# Sensor_Board.net
KiCad netlist of a schematic drawn in EAGLE
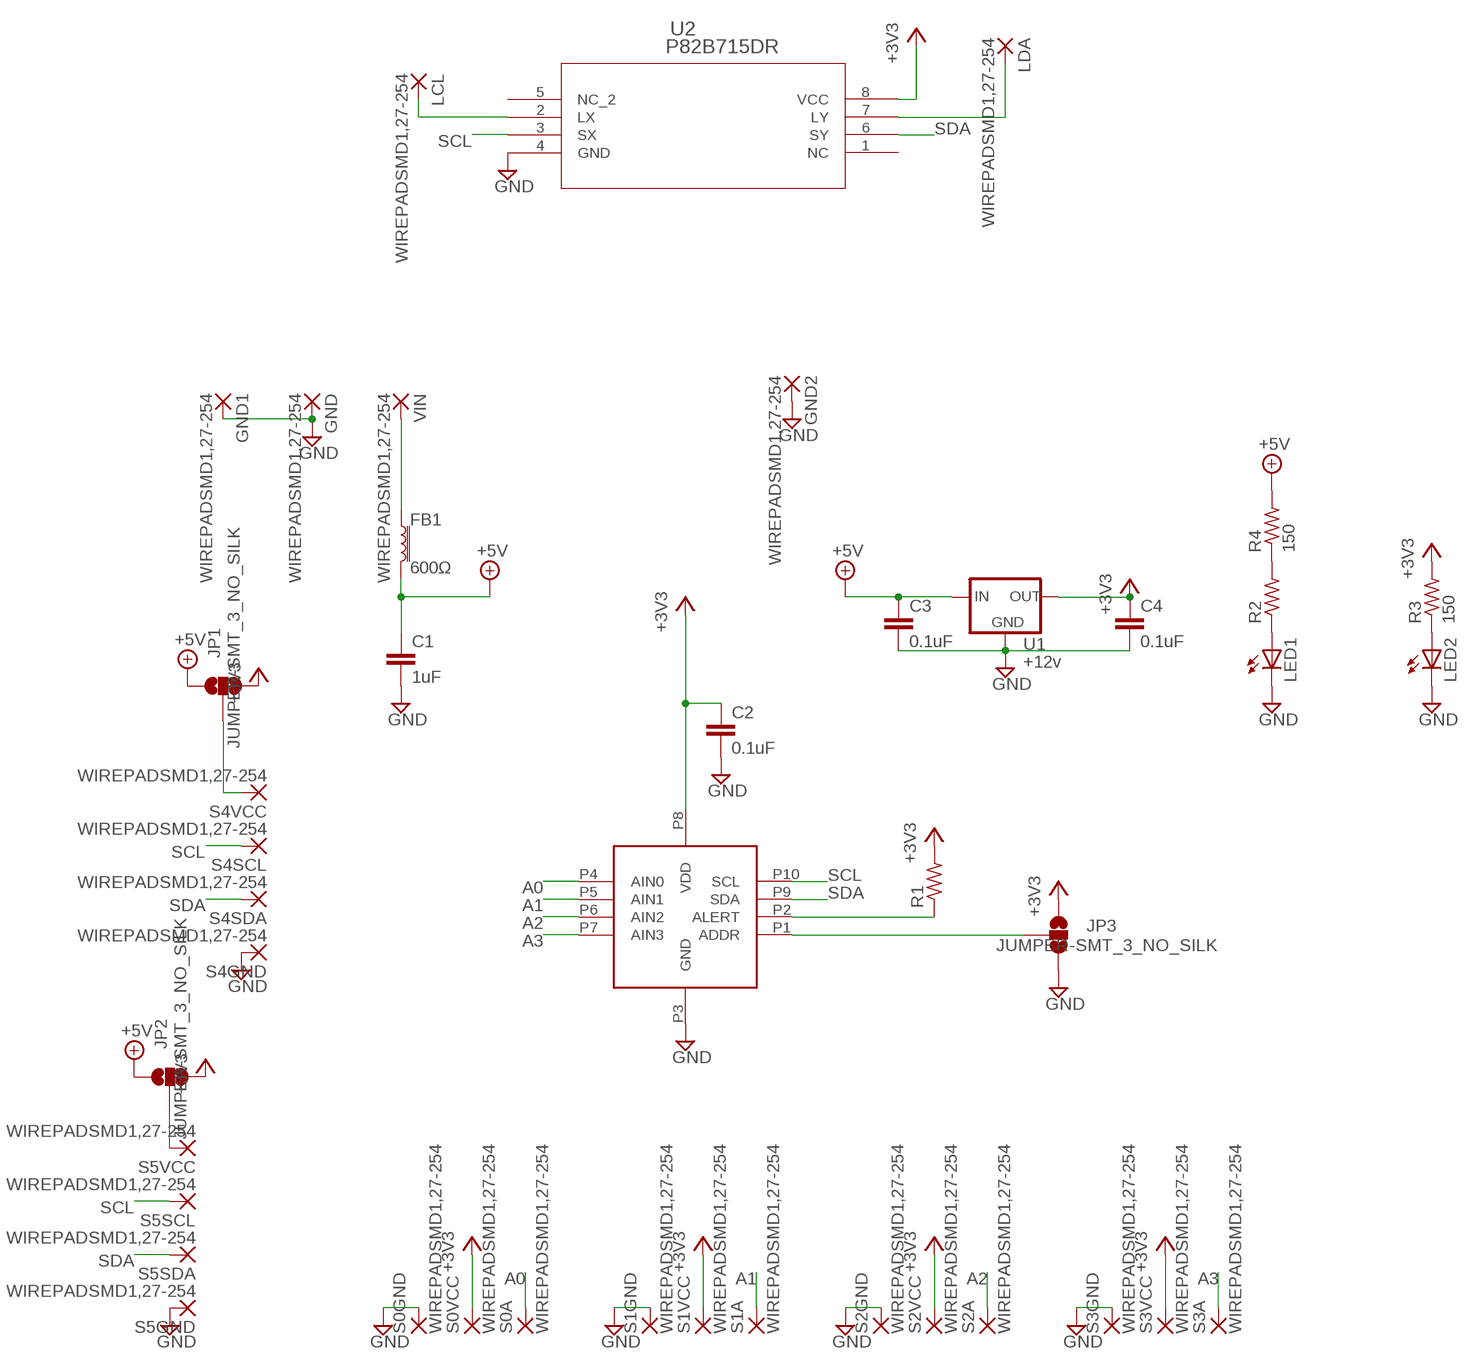
[diagram p0: schematic, sheet 1]

(export (version "E")
  (design (tool "Eeschema 10.0.6"))
  (components
    (comp (ref "C1")
      (value "1uF")
      (footprint "eagle-import:C0805")
      (libsource (lib "eagle-import") (part "C-EUC0805"))
    )
    (comp (ref "C2")
      (value "0.1uF")
      (footprint "eagle-import:C0805")
      (libsource (lib "eagle-import") (part "C-EUC0805"))
    )
    (comp (ref "C3")
      (value "0.1uF")
      (footprint "eagle-import:C0805")
      (libsource (lib "eagle-import") (part "C-EUC0805"))
    )
    (comp (ref "C4")
      (value "0.1uF")
      (footprint "eagle-import:C0805")
      (libsource (lib "eagle-import") (part "C-EUC0805"))
    )
    (comp (ref "FB1")
      (value "600Ω")
      (footprint "eagle-import:0805")
      (libsource (lib "eagle-import") (part "FERRITE_BEAD-0805-600Ω-100MHZ"))
    )
    (comp (ref "GND")
      (value "WIREPADSMD1,27-254")
      (footprint "eagle-import:SMD1,27-2,54")
      (libsource (lib "eagle-import") (part "WIREPADSMD1,27-254"))
    )
    (comp (ref "GND1")
      (value "WIREPADSMD1,27-254")
      (footprint "eagle-import:SMD1,27-2,54")
      (libsource (lib "eagle-import") (part "WIREPADSMD1,27-254"))
    )
    (comp (ref "GND2")
      (value "WIREPADSMD1,27-254")
      (footprint "eagle-import:SMD1,27-2,54")
      (libsource (lib "eagle-import") (part "WIREPADSMD1,27-254"))
    )
    (comp (ref "JP1")
      (value "JUMPER-SMT_3_NO_SILK")
      (footprint "eagle-import:SMT-JUMPER_3_NO_SILK")
      (libsource (lib "eagle-import") (part "JUMPER-SMT_3_NO_SILK"))
    )
    (comp (ref "JP2")
      (value "JUMPER-SMT_3_NO_SILK")
      (footprint "eagle-import:SMT-JUMPER_3_NO_SILK")
      (libsource (lib "eagle-import") (part "JUMPER-SMT_3_NO_SILK"))
    )
    (comp (ref "JP3")
      (value "JUMPER-SMT_3_NO_SILK")
      (footprint "eagle-import:SMT-JUMPER_3_NO_SILK")
      (libsource (lib "eagle-import") (part "JUMPER-SMT_3_NO_SILK"))
    )
    (comp (ref "LCL")
      (value "WIREPADSMD1,27-254")
      (footprint "eagle-import:SMD1,27-2,54")
      (libsource (lib "eagle-import") (part "WIREPADSMD1,27-254"))
    )
    (comp (ref "LDA")
      (value "WIREPADSMD1,27-254")
      (footprint "eagle-import:SMD1,27-2,54")
      (libsource (lib "eagle-import") (part "WIREPADSMD1,27-254"))
    )
    (comp (ref "LED1")
      (value "LEDCHIP-LED0805")
      (footprint "eagle-import:CHIP-LED0805")
      (libsource (lib "eagle-import") (part "LEDCHIP-LED0805"))
    )
    (comp (ref "LED2")
      (value "LEDCHIP-LED0805")
      (footprint "eagle-import:CHIP-LED0805")
      (libsource (lib "eagle-import") (part "LEDCHIP-LED0805"))
    )
    (comp (ref "R1")
      (value "R-US_R0805")
      (footprint "eagle-import:R0805")
      (libsource (lib "eagle-import") (part "R-US_R0805"))
    )
    (comp (ref "R2")
      (value "R-US_R0805")
      (footprint "eagle-import:R0805")
      (libsource (lib "eagle-import") (part "R-US_R0805"))
    )
    (comp (ref "R3")
      (value "150")
      (footprint "eagle-import:R0805")
      (libsource (lib "eagle-import") (part "R-US_R0805"))
    )
    (comp (ref "R4")
      (value "150")
      (footprint "eagle-import:R0805")
      (libsource (lib "eagle-import") (part "R-US_R0805"))
    )
    (comp (ref "S0A")
      (value "WIREPADSMD1,27-254")
      (footprint "eagle-import:SMD1,27-2,54")
      (libsource (lib "eagle-import") (part "WIREPADSMD1,27-254"))
    )
    (comp (ref "S0GND")
      (value "WIREPADSMD1,27-254")
      (footprint "eagle-import:SMD1,27-2,54")
      (libsource (lib "eagle-import") (part "WIREPADSMD1,27-254"))
    )
    (comp (ref "S0VCC")
      (value "WIREPADSMD1,27-254")
      (footprint "eagle-import:SMD1,27-2,54")
      (libsource (lib "eagle-import") (part "WIREPADSMD1,27-254"))
    )
    (comp (ref "S1A")
      (value "WIREPADSMD1,27-254")
      (footprint "eagle-import:SMD1,27-2,54")
      (libsource (lib "eagle-import") (part "WIREPADSMD1,27-254"))
    )
    (comp (ref "S1GND")
      (value "WIREPADSMD1,27-254")
      (footprint "eagle-import:SMD1,27-2,54")
      (libsource (lib "eagle-import") (part "WIREPADSMD1,27-254"))
    )
    (comp (ref "S1VCC")
      (value "WIREPADSMD1,27-254")
      (footprint "eagle-import:SMD1,27-2,54")
      (libsource (lib "eagle-import") (part "WIREPADSMD1,27-254"))
    )
    (comp (ref "S2A")
      (value "WIREPADSMD1,27-254")
      (footprint "eagle-import:SMD1,27-2,54")
      (libsource (lib "eagle-import") (part "WIREPADSMD1,27-254"))
    )
    (comp (ref "S2GND")
      (value "WIREPADSMD1,27-254")
      (footprint "eagle-import:SMD1,27-2,54")
      (libsource (lib "eagle-import") (part "WIREPADSMD1,27-254"))
    )
    (comp (ref "S2VCC")
      (value "WIREPADSMD1,27-254")
      (footprint "eagle-import:SMD1,27-2,54")
      (libsource (lib "eagle-import") (part "WIREPADSMD1,27-254"))
    )
    (comp (ref "S3A")
      (value "WIREPADSMD1,27-254")
      (footprint "eagle-import:SMD1,27-2,54")
      (libsource (lib "eagle-import") (part "WIREPADSMD1,27-254"))
    )
    (comp (ref "S3GND")
      (value "WIREPADSMD1,27-254")
      (footprint "eagle-import:SMD1,27-2,54")
      (libsource (lib "eagle-import") (part "WIREPADSMD1,27-254"))
    )
    (comp (ref "S3VCC")
      (value "WIREPADSMD1,27-254")
      (footprint "eagle-import:SMD1,27-2,54")
      (libsource (lib "eagle-import") (part "WIREPADSMD1,27-254"))
    )
    (comp (ref "S4GND")
      (value "WIREPADSMD1,27-254")
      (footprint "eagle-import:SMD1,27-2,54")
      (libsource (lib "eagle-import") (part "WIREPADSMD1,27-254"))
    )
    (comp (ref "S4SCL")
      (value "WIREPADSMD1,27-254")
      (footprint "eagle-import:SMD1,27-2,54")
      (libsource (lib "eagle-import") (part "WIREPADSMD1,27-254"))
    )
    (comp (ref "S4SDA")
      (value "WIREPADSMD1,27-254")
      (footprint "eagle-import:SMD1,27-2,54")
      (libsource (lib "eagle-import") (part "WIREPADSMD1,27-254"))
    )
    (comp (ref "S4VCC")
      (value "WIREPADSMD1,27-254")
      (footprint "eagle-import:SMD1,27-2,54")
      (libsource (lib "eagle-import") (part "WIREPADSMD1,27-254"))
    )
    (comp (ref "S5GND")
      (value "WIREPADSMD1,27-254")
      (footprint "eagle-import:SMD1,27-2,54")
      (libsource (lib "eagle-import") (part "WIREPADSMD1,27-254"))
    )
    (comp (ref "S5SCL")
      (value "WIREPADSMD1,27-254")
      (footprint "eagle-import:SMD1,27-2,54")
      (libsource (lib "eagle-import") (part "WIREPADSMD1,27-254"))
    )
    (comp (ref "S5SDA")
      (value "WIREPADSMD1,27-254")
      (footprint "eagle-import:SMD1,27-2,54")
      (libsource (lib "eagle-import") (part "WIREPADSMD1,27-254"))
    )
    (comp (ref "S5VCC")
      (value "WIREPADSMD1,27-254")
      (footprint "eagle-import:SMD1,27-2,54")
      (libsource (lib "eagle-import") (part "WIREPADSMD1,27-254"))
    )
    (comp (ref "U1")
      (value "+12v")
      (footprint "eagle-import:TO-252")
      (libsource (lib "eagle-import") (part "V_REG_78XX7812"))
    )
    (comp (ref "U2")
      (value "P82B715DR")
      (footprint "eagle-import:SO-08")
      (libsource (lib "eagle-import") (part "P82B715DR"))
    )
    (comp (ref "U3")
      (value "ADS1115")
      (footprint "eagle-import:VSSOP-10")
      (libsource (lib "eagle-import") (part "ADS1115"))
    )
    (comp (ref "VIN")
      (value "WIREPADSMD1,27-254")
      (footprint "eagle-import:SMD1,27-2,54")
      (libsource (lib "eagle-import") (part "WIREPADSMD1,27-254"))
    )
  )
  (nets
    (net (code "1") (name "+3V3") (class "Default")
      (node (ref "C2") (pin "1") (pinfunction "1_1") (pintype "passive"))
      (node (ref "C4") (pin "1") (pinfunction "1_1") (pintype "passive"))
      (node (ref "JP1") (pin "3") (pinfunction "3_3") (pintype "passive"))
      (node (ref "JP2") (pin "3") (pinfunction "3_3") (pintype "passive"))
      (node (ref "JP3") (pin "1") (pinfunction "1_1") (pintype "passive"))
      (node (ref "R1") (pin "2") (pinfunction "2_2") (pintype "passive"))
      (node (ref "R3") (pin "2") (pinfunction "2_2") (pintype "passive"))
      (node (ref "S0VCC") (pin "1") (pinfunction "P_1") (pintype "passive"))
      (node (ref "S1VCC") (pin "1") (pinfunction "P_1") (pintype "passive"))
      (node (ref "S2VCC") (pin "1") (pinfunction "P_1") (pintype "passive"))
      (node (ref "S3VCC") (pin "1") (pinfunction "P_1") (pintype "passive"))
      (node (ref "U1") (pin "2") (pinfunction "OUT_2") (pintype "passive"))
      (node (ref "U2") (pin "8") (pinfunction "VCC_8") (pintype "power_in"))
      (node (ref "U3") (pin "P8") (pinfunction "VDD_P8") (pintype "power_in"))
    )
    (net (code "2") (name "+5V") (class "Default")
      (node (ref "C1") (pin "1") (pinfunction "1_1") (pintype "passive"))
      (node (ref "C3") (pin "1") (pinfunction "1_1") (pintype "passive"))
      (node (ref "FB1") (pin "2") (pinfunction "2_2") (pintype "passive"))
      (node (ref "JP1") (pin "1") (pinfunction "1_1") (pintype "passive"))
      (node (ref "JP2") (pin "1") (pinfunction "1_1") (pintype "passive"))
      (node (ref "R4") (pin "2") (pinfunction "2_2") (pintype "passive"))
      (node (ref "U1") (pin "1") (pinfunction "IN_1") (pintype "input"))
    )
    (net (code "3") (name "/A0") (class "Default")
      (node (ref "S0A") (pin "1") (pinfunction "P_1") (pintype "passive"))
      (node (ref "U3") (pin "P4") (pinfunction "AIN0_P4") (pintype "input"))
    )
    (net (code "4") (name "/A1") (class "Default")
      (node (ref "S1A") (pin "1") (pinfunction "P_1") (pintype "passive"))
      (node (ref "U3") (pin "P5") (pinfunction "AIN1_P5") (pintype "input"))
    )
    (net (code "5") (name "/A2") (class "Default")
      (node (ref "S2A") (pin "1") (pinfunction "P_1") (pintype "passive"))
      (node (ref "U3") (pin "P6") (pinfunction "AIN2_P6") (pintype "input"))
    )
    (net (code "6") (name "/A3") (class "Default")
      (node (ref "S3A") (pin "1") (pinfunction "P_1") (pintype "passive"))
      (node (ref "U3") (pin "P7") (pinfunction "AIN3_P7") (pintype "input"))
    )
    (net (code "7") (name "/SCL") (class "Default")
      (node (ref "S4SCL") (pin "1") (pinfunction "P_1") (pintype "passive"))
      (node (ref "S5SCL") (pin "1") (pinfunction "P_1") (pintype "passive"))
      (node (ref "U2") (pin "3") (pinfunction "SX_3") (pintype "passive"))
      (node (ref "U3") (pin "P10") (pinfunction "SCL_P10") (pintype "bidirectional"))
    )
    (net (code "8") (name "/SDA") (class "Default")
      (node (ref "S4SDA") (pin "1") (pinfunction "P_1") (pintype "passive"))
      (node (ref "S5SDA") (pin "1") (pinfunction "P_1") (pintype "passive"))
      (node (ref "U2") (pin "6") (pinfunction "SY_6") (pintype "passive"))
      (node (ref "U3") (pin "P9") (pinfunction "SDA_P9") (pintype "bidirectional"))
    )
    (net (code "9") (name "GND") (class "Default")
      (node (ref "C1") (pin "2") (pinfunction "2_2") (pintype "passive"))
      (node (ref "C2") (pin "2") (pinfunction "2_2") (pintype "passive"))
      (node (ref "C3") (pin "2") (pinfunction "2_2") (pintype "passive"))
      (node (ref "C4") (pin "2") (pinfunction "2_2") (pintype "passive"))
      (node (ref "GND") (pin "1") (pinfunction "P_1") (pintype "passive"))
      (node (ref "GND1") (pin "1") (pinfunction "P_1") (pintype "passive"))
      (node (ref "GND2") (pin "1") (pinfunction "P_1") (pintype "passive"))
      (node (ref "JP3") (pin "3") (pinfunction "3_3") (pintype "passive"))
      (node (ref "LED1") (pin "C") (pinfunction "C_C") (pintype "passive"))
      (node (ref "LED2") (pin "C") (pinfunction "C_C") (pintype "passive"))
      (node (ref "S0GND") (pin "1") (pinfunction "P_1") (pintype "passive"))
      (node (ref "S1GND") (pin "1") (pinfunction "P_1") (pintype "passive"))
      (node (ref "S2GND") (pin "1") (pinfunction "P_1") (pintype "passive"))
      (node (ref "S3GND") (pin "1") (pinfunction "P_1") (pintype "passive"))
      (node (ref "S4GND") (pin "1") (pinfunction "P_1") (pintype "passive"))
      (node (ref "S5GND") (pin "1") (pinfunction "P_1") (pintype "passive"))
      (node (ref "U1") (pin "3") (pinfunction "GND_3") (pintype "input"))
      (node (ref "U2") (pin "4") (pinfunction "GND_4") (pintype "power_in"))
      (node (ref "U3") (pin "P3") (pinfunction "GND_P3") (pintype "power_in"))
    )
    (net (code "10") (name "Net-(LCL-P)") (class "Default")
      (node (ref "LCL") (pin "1") (pinfunction "P_1") (pintype "passive"))
      (node (ref "U2") (pin "2") (pinfunction "LX_2") (pintype "passive"))
    )
    (net (code "11") (name "Net-(LDA-P)") (class "Default")
      (node (ref "LDA") (pin "1") (pinfunction "P_1") (pintype "passive"))
      (node (ref "U2") (pin "7") (pinfunction "LY_7") (pintype "passive"))
    )
    (net (code "12") (name "Net-(LED1-PadA)") (class "Default")
      (node (ref "LED1") (pin "A") (pinfunction "A_A") (pintype "passive"))
      (node (ref "R2") (pin "1") (pinfunction "1_1") (pintype "passive"))
    )
    (net (code "13") (name "Net-(LED2-PadA)") (class "Default")
      (node (ref "LED2") (pin "A") (pinfunction "A_A") (pintype "passive"))
      (node (ref "R3") (pin "1") (pinfunction "1_1") (pintype "passive"))
    )
    (net (code "14") (name "Net-(R2-Pad2)") (class "Default")
      (node (ref "R2") (pin "2") (pinfunction "2_2") (pintype "passive"))
      (node (ref "R4") (pin "1") (pinfunction "1_1") (pintype "passive"))
    )
    (net (code "15") (name "Net-(S4VCC-P)") (class "Default")
      (node (ref "JP1") (pin "2") (pinfunction "2_2") (pintype "passive"))
      (node (ref "S4VCC") (pin "1") (pinfunction "P_1") (pintype "passive"))
    )
    (net (code "16") (name "Net-(S5VCC-P)") (class "Default")
      (node (ref "JP2") (pin "2") (pinfunction "2_2") (pintype "passive"))
      (node (ref "S5VCC") (pin "1") (pinfunction "P_1") (pintype "passive"))
    )
    (net (code "17") (name "Net-(U3-ADDR)") (class "Default")
      (node (ref "JP3") (pin "2") (pinfunction "2_2") (pintype "passive"))
      (node (ref "U3") (pin "P1") (pinfunction "ADDR_P1") (pintype "bidirectional"))
    )
    (net (code "18") (name "Net-(U3-ALERT)") (class "Default")
      (node (ref "R1") (pin "1") (pinfunction "1_1") (pintype "passive"))
      (node (ref "U3") (pin "P2") (pinfunction "ALERT_P2") (pintype "bidirectional"))
    )
    (net (code "19") (name "Net-(VIN-P)") (class "Default")
      (node (ref "FB1") (pin "1") (pinfunction "1_1") (pintype "passive"))
      (node (ref "VIN") (pin "1") (pinfunction "P_1") (pintype "passive"))
    )
    (net (code "20") (name "unconnected-(U2-NC-Pad1)") (class "Default")
      (node (ref "U2") (pin "1") (pinfunction "NC_1") (pintype "passive"))
    )
    (net (code "21") (name "unconnected-(U2-NC_2-Pad5)") (class "Default")
      (node (ref "U2") (pin "5") (pinfunction "NC_2_5") (pintype "passive"))
    )
  )
)
